# Adafruit_RGB_Matrix_FeatherWing_nRF52.net
KiCad netlist of a schematic drawn in EAGLE
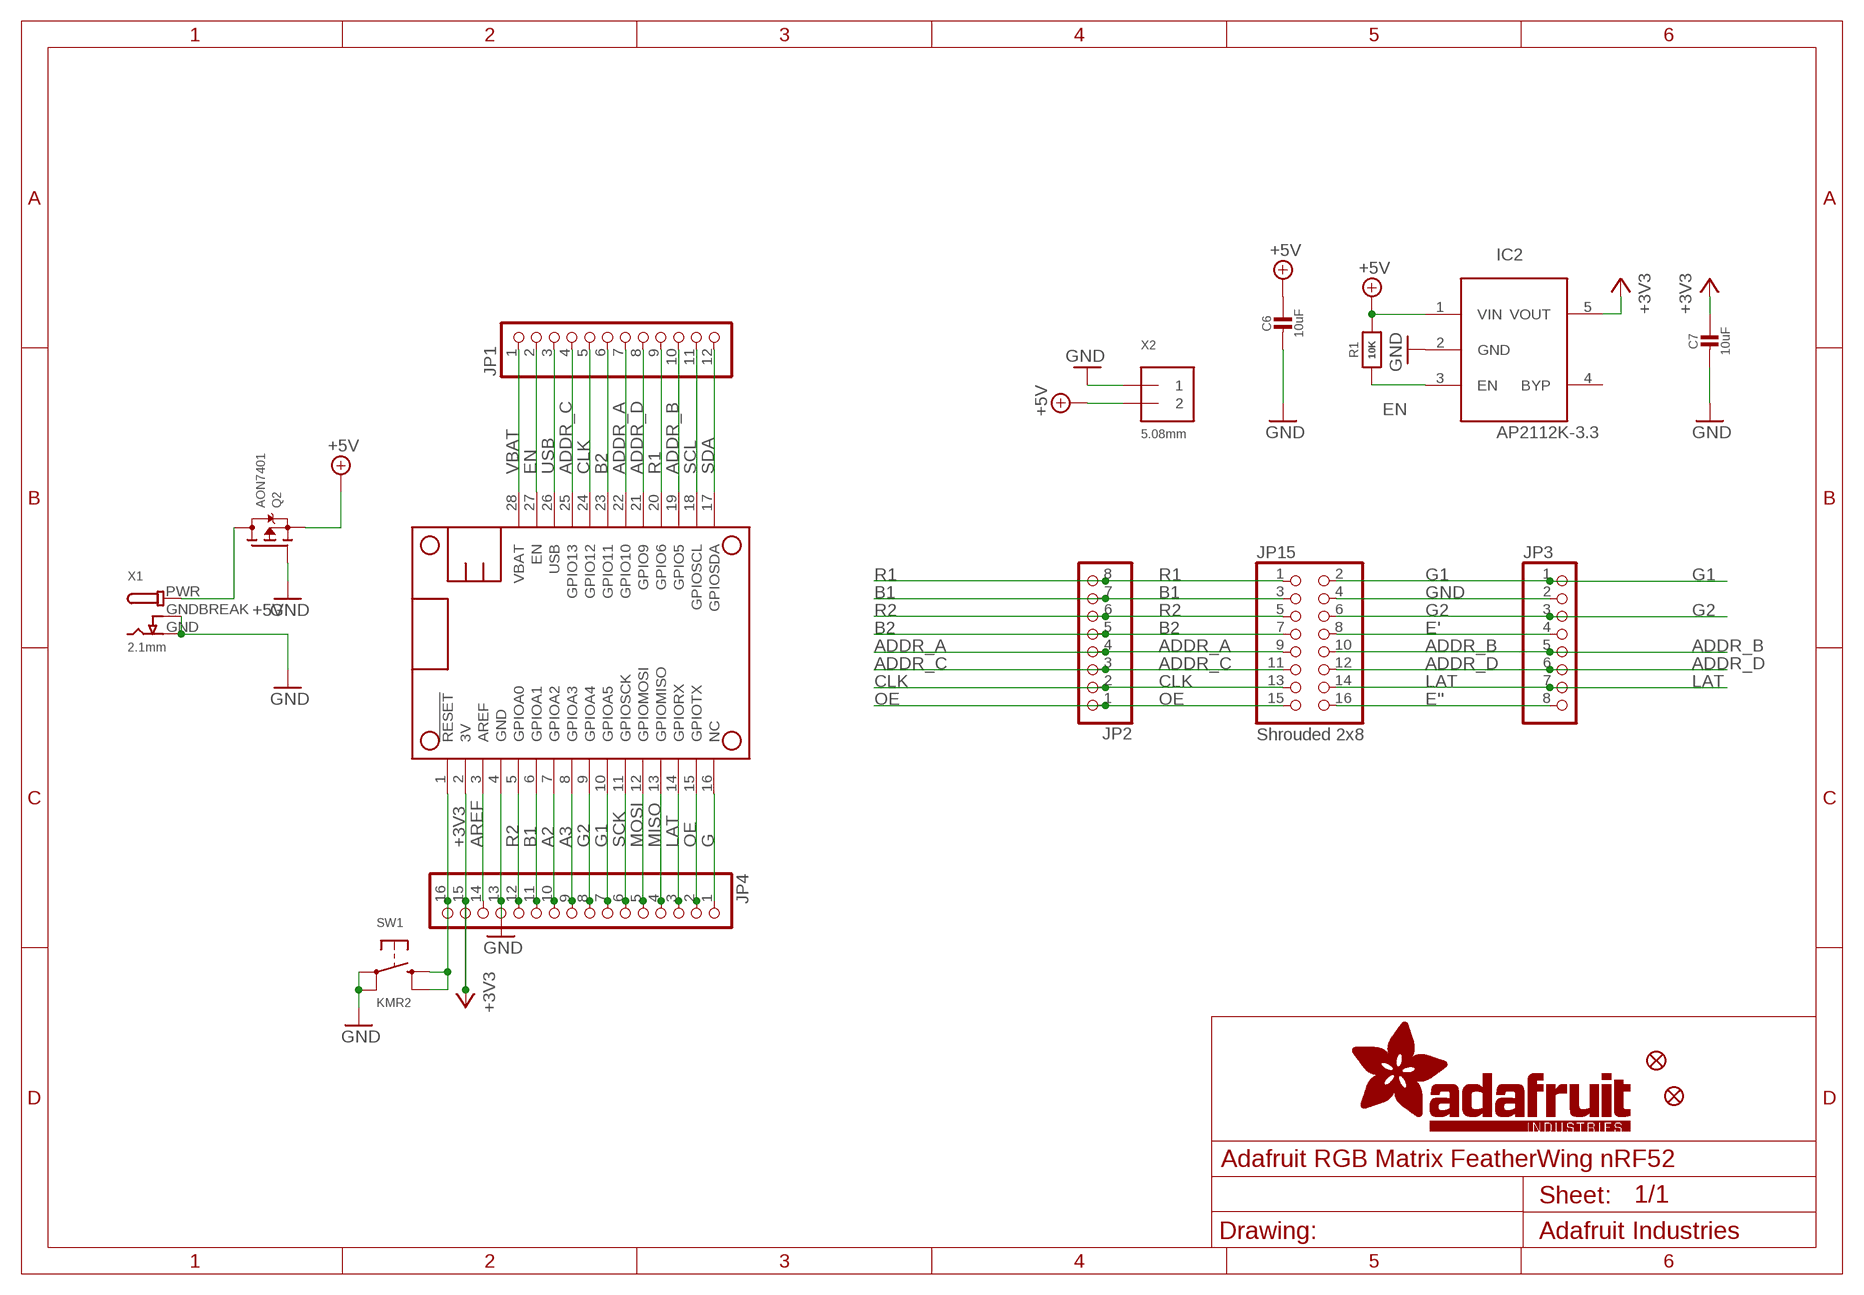
[diagram p0: schematic, sheet 1]

(export (version "E")
  (design (tool "Eeschema 10.0.6"))
  (components
    (comp (ref "C6")
      (value "10uF")
      (footprint "eagle-import:0805-NO")
      (libsource (lib "eagle-import") (part "CAP_CERAMIC0805-NOOUTLINE"))
    )
    (comp (ref "C7")
      (value "10uF")
      (footprint "eagle-import:0805-NO")
      (libsource (lib "eagle-import") (part "CAP_CERAMIC0805-NOOUTLINE"))
    )
    (comp (ref "FID1")
      (value "FIDUCIAL_1MM")
      (footprint "eagle-import:FIDUCIAL_1MM")
      (libsource (lib "eagle-import") (part "FIDUCIAL_1MM"))
    )
    (comp (ref "FID3")
      (value "FIDUCIAL_1MM")
      (footprint "eagle-import:FIDUCIAL_1MM")
      (libsource (lib "eagle-import") (part "FIDUCIAL_1MM"))
    )
    (comp (ref "IC2")
      (value "AP2112K-3.3")
      (footprint "eagle-import:SOT23-5L")
      (libsource (lib "eagle-import") (part "LP298XS"))
    )
    (comp (ref "JP1")
      (value "HEADER-1X12")
      (footprint "eagle-import:1X12_ROUND")
      (libsource (lib "eagle-import") (part "HEADER-1X12"))
    )
    (comp (ref "JP2")
      (value "HEADER-1X870MIL")
      (footprint "eagle-import:1X08_ROUND_70")
      (libsource (lib "eagle-import") (part "HEADER-1X870MIL"))
    )
    (comp (ref "JP3")
      (value "HEADER-1X870MIL")
      (footprint "eagle-import:1X08_ROUND_70")
      (libsource (lib "eagle-import") (part "HEADER-1X870MIL"))
    )
    (comp (ref "JP4")
      (value "HEADER-1X16ROUND")
      (footprint "eagle-import:1X16_ROUND")
      (libsource (lib "eagle-import") (part "HEADER-1X16ROUND"))
    )
    (comp (ref "JP15")
      (value "Shrouded 2x8")
      (footprint "eagle-import:2X08_SHROUDED")
      (libsource (lib "eagle-import") (part "HEADER-2X8_SHROUDED"))
    )
    (comp (ref "MS1")
      (value "FEATHERWING")
      (footprint "eagle-import:FEATHERWING")
      (libsource (lib "eagle-import") (part "FEATHERWING"))
    )
    (comp (ref "Q2")
      (value "AON7401")
      (footprint "eagle-import:POWERDI3333")
      (libsource (lib "eagle-import") (part "MOSFET-P-POWERDI3333"))
    )
    (comp (ref "R1")
      (value "10K")
      (footprint "eagle-import:0603-NO")
      (libsource (lib "eagle-import") (part "RESISTOR_0603_NOOUT"))
    )
    (comp (ref "SW1")
      (value "KMR2")
      (footprint "eagle-import:BTN_KMR2_4.6X2.8")
      (libsource (lib "eagle-import") (part "SWITCH_TACT_SMT4.6X2.8"))
    )
    (comp (ref "X1")
      (value "2.1mm")
      (footprint "eagle-import:DCJACK_2MM_PTH")
      (libsource (lib "eagle-import") (part "DCBARRELPTH"))
    )
    (comp (ref "X2")
      (value "5.08mm")
      (footprint "eagle-import:TERMBLOCK_508_1X2")
      (libsource (lib "eagle-import") (part "TERMBLOCK_1X2_5.08MM"))
    )
  )
  (nets
    (net (code "1") (name "+3V3") (class "Default")
      (node (ref "C7") (pin "1") (pinfunction "1_1") (pintype "passive"))
      (node (ref "IC2") (pin "5") (pinfunction "VOUT_5") (pintype "bidirectional"))
      (node (ref "JP4") (pin "15") (pinfunction "15_15") (pintype "passive"))
      (node (ref "MS1") (pin "2") (pinfunction "3V_2") (pintype "power_in"))
    )
    (net (code "2") (name "+5V") (class "Default")
      (node (ref "C6") (pin "1") (pinfunction "1_1") (pintype "passive"))
      (node (ref "IC2") (pin "1") (pinfunction "VIN_1") (pintype "bidirectional"))
      (node (ref "Q2") (pin "1") (pinfunction "S_1") (pintype "passive"))
      (node (ref "Q2") (pin "2") (pinfunction "S_2") (pintype "passive"))
      (node (ref "Q2") (pin "3") (pinfunction "S_3") (pintype "passive"))
      (node (ref "R1") (pin "2") (pinfunction "2_2") (pintype "passive"))
      (node (ref "X2") (pin "P$4") (pinfunction "2_P$4") (pintype "passive"))
    )
    (net (code "3") (name "/A2") (class "Default")
      (node (ref "JP4") (pin "10") (pinfunction "10_10") (pintype "passive"))
      (node (ref "MS1") (pin "7") (pinfunction "GPIOA2_7") (pintype "bidirectional"))
    )
    (net (code "4") (name "/A3") (class "Default")
      (node (ref "JP4") (pin "9") (pinfunction "9_9") (pintype "passive"))
      (node (ref "MS1") (pin "8") (pinfunction "GPIOA3_8") (pintype "bidirectional"))
    )
    (net (code "5") (name "/ADDR_A") (class "Default")
      (node (ref "JP1") (pin "7") (pinfunction "7_7") (pintype "passive"))
      (node (ref "JP15") (pin "9") (pinfunction "9_9") (pintype "passive"))
      (node (ref "JP2") (pin "4") (pinfunction "4_4") (pintype "passive"))
      (node (ref "MS1") (pin "22") (pinfunction "GPIO10_22") (pintype "bidirectional"))
    )
    (net (code "6") (name "/ADDR_B") (class "Default")
      (node (ref "JP1") (pin "10") (pinfunction "10_10") (pintype "passive"))
      (node (ref "JP15") (pin "10") (pinfunction "10_10") (pintype "passive"))
      (node (ref "JP3") (pin "5") (pinfunction "5_5") (pintype "passive"))
      (node (ref "MS1") (pin "19") (pinfunction "GPIO5_19") (pintype "bidirectional"))
    )
    (net (code "7") (name "/ADDR_C") (class "Default")
      (node (ref "JP1") (pin "4") (pinfunction "4_4") (pintype "passive"))
      (node (ref "JP15") (pin "11") (pinfunction "11_11") (pintype "passive"))
      (node (ref "JP2") (pin "3") (pinfunction "3_3") (pintype "passive"))
      (node (ref "MS1") (pin "25") (pinfunction "GPIO13_25") (pintype "bidirectional"))
    )
    (net (code "8") (name "/ADDR_D") (class "Default")
      (node (ref "JP1") (pin "8") (pinfunction "8_8") (pintype "passive"))
      (node (ref "JP15") (pin "12") (pinfunction "12_12") (pintype "passive"))
      (node (ref "JP3") (pin "6") (pinfunction "6_6") (pintype "passive"))
      (node (ref "MS1") (pin "21") (pinfunction "GPIO9_21") (pintype "bidirectional"))
    )
    (net (code "9") (name "/AREF") (class "Default")
      (node (ref "JP4") (pin "14") (pinfunction "14_14") (pintype "passive"))
      (node (ref "MS1") (pin "3") (pinfunction "AREF_3") (pintype "passive"))
    )
    (net (code "10") (name "/B1") (class "Default")
      (node (ref "JP15") (pin "3") (pinfunction "3_3") (pintype "passive"))
      (node (ref "JP2") (pin "7") (pinfunction "7_7") (pintype "passive"))
      (node (ref "JP4") (pin "11") (pinfunction "11_11") (pintype "passive"))
      (node (ref "MS1") (pin "6") (pinfunction "GPIOA1_6") (pintype "bidirectional"))
    )
    (net (code "11") (name "/B2") (class "Default")
      (node (ref "JP1") (pin "6") (pinfunction "6_6") (pintype "passive"))
      (node (ref "JP15") (pin "7") (pinfunction "7_7") (pintype "passive"))
      (node (ref "JP2") (pin "5") (pinfunction "5_5") (pintype "passive"))
      (node (ref "MS1") (pin "23") (pinfunction "GPIO11_23") (pintype "bidirectional"))
    )
    (net (code "12") (name "/CLK") (class "Default")
      (node (ref "JP1") (pin "5") (pinfunction "5_5") (pintype "passive"))
      (node (ref "JP15") (pin "13") (pinfunction "13_13") (pintype "passive"))
      (node (ref "JP2") (pin "2") (pinfunction "2_2") (pintype "passive"))
      (node (ref "MS1") (pin "24") (pinfunction "GPIO12_24") (pintype "bidirectional"))
    )
    (net (code "13") (name "/E'") (class "Default")
      (node (ref "JP15") (pin "8") (pinfunction "8_8") (pintype "passive"))
      (node (ref "JP3") (pin "4") (pinfunction "4_4") (pintype "passive"))
    )
    (net (code "14") (name "/E''") (class "Default")
      (node (ref "JP15") (pin "16") (pinfunction "16_16") (pintype "passive"))
      (node (ref "JP3") (pin "8") (pinfunction "8_8") (pintype "passive"))
    )
    (net (code "15") (name "/EN") (class "Default")
      (node (ref "IC2") (pin "3") (pinfunction "EN_3") (pintype "bidirectional"))
      (node (ref "JP1") (pin "2") (pinfunction "2_2") (pintype "passive"))
      (node (ref "MS1") (pin "27") (pinfunction "EN_27") (pintype "passive"))
      (node (ref "R1") (pin "1") (pinfunction "1_1") (pintype "passive"))
    )
    (net (code "16") (name "/G") (class "Default")
      (node (ref "JP4") (pin "1") (pinfunction "1_1") (pintype "passive"))
      (node (ref "MS1") (pin "16") (pinfunction "NC_16") (pintype "passive"))
    )
    (net (code "17") (name "/G1") (class "Default")
      (node (ref "JP15") (pin "2") (pinfunction "2_2") (pintype "passive"))
      (node (ref "JP3") (pin "1") (pinfunction "1_1") (pintype "passive"))
      (node (ref "JP4") (pin "7") (pinfunction "7_7") (pintype "passive"))
      (node (ref "MS1") (pin "10") (pinfunction "GPIOA5_10") (pintype "bidirectional"))
    )
    (net (code "18") (name "/G2") (class "Default")
      (node (ref "JP15") (pin "6") (pinfunction "6_6") (pintype "passive"))
      (node (ref "JP3") (pin "3") (pinfunction "3_3") (pintype "passive"))
      (node (ref "JP4") (pin "8") (pinfunction "8_8") (pintype "passive"))
      (node (ref "MS1") (pin "9") (pinfunction "GPIOA4_9") (pintype "bidirectional"))
    )
    (net (code "19") (name "/LAT") (class "Default")
      (node (ref "JP15") (pin "14") (pinfunction "14_14") (pintype "passive"))
      (node (ref "JP3") (pin "7") (pinfunction "7_7") (pintype "passive"))
      (node (ref "JP4") (pin "3") (pinfunction "3_3") (pintype "passive"))
      (node (ref "MS1") (pin "14") (pinfunction "GPIORX_14") (pintype "bidirectional"))
    )
    (net (code "20") (name "/MISO") (class "Default")
      (node (ref "JP4") (pin "4") (pinfunction "4_4") (pintype "passive"))
      (node (ref "MS1") (pin "13") (pinfunction "GPIOMISO_13") (pintype "bidirectional"))
    )
    (net (code "21") (name "/MOSI") (class "Default")
      (node (ref "JP4") (pin "5") (pinfunction "5_5") (pintype "passive"))
      (node (ref "MS1") (pin "12") (pinfunction "GPIOMOSI_12") (pintype "bidirectional"))
    )
    (net (code "22") (name "/OE") (class "Default")
      (node (ref "JP15") (pin "15") (pinfunction "15_15") (pintype "passive"))
      (node (ref "JP2") (pin "1") (pinfunction "1_1") (pintype "passive"))
      (node (ref "JP4") (pin "2") (pinfunction "2_2") (pintype "passive"))
      (node (ref "MS1") (pin "15") (pinfunction "GPIOTX_15") (pintype "bidirectional"))
    )
    (net (code "23") (name "/R1") (class "Default")
      (node (ref "JP1") (pin "9") (pinfunction "9_9") (pintype "passive"))
      (node (ref "JP15") (pin "1") (pinfunction "1_1") (pintype "passive"))
      (node (ref "JP2") (pin "8") (pinfunction "8_8") (pintype "passive"))
      (node (ref "MS1") (pin "20") (pinfunction "GPIO6_20") (pintype "bidirectional"))
    )
    (net (code "24") (name "/R2") (class "Default")
      (node (ref "JP15") (pin "5") (pinfunction "5_5") (pintype "passive"))
      (node (ref "JP2") (pin "6") (pinfunction "6_6") (pintype "passive"))
      (node (ref "JP4") (pin "12") (pinfunction "12_12") (pintype "passive"))
      (node (ref "MS1") (pin "5") (pinfunction "GPIOA0_5") (pintype "bidirectional"))
    )
    (net (code "25") (name "/SCK") (class "Default")
      (node (ref "JP4") (pin "6") (pinfunction "6_6") (pintype "passive"))
      (node (ref "MS1") (pin "11") (pinfunction "GPIOSCK_11") (pintype "bidirectional"))
    )
    (net (code "26") (name "/SCL") (class "Default")
      (node (ref "JP1") (pin "11") (pinfunction "11_11") (pintype "passive"))
      (node (ref "MS1") (pin "18") (pinfunction "GPIOSCL_18") (pintype "bidirectional"))
    )
    (net (code "27") (name "/SDA") (class "Default")
      (node (ref "JP1") (pin "12") (pinfunction "12_12") (pintype "passive"))
      (node (ref "MS1") (pin "17") (pinfunction "GPIOSDA_17") (pintype "bidirectional"))
    )
    (net (code "28") (name "/USB") (class "Default")
      (node (ref "JP1") (pin "3") (pinfunction "3_3") (pintype "passive"))
      (node (ref "MS1") (pin "26") (pinfunction "USB_26") (pintype "power_in"))
    )
    (net (code "29") (name "/VBAT") (class "Default")
      (node (ref "JP1") (pin "1") (pinfunction "1_1") (pintype "passive"))
      (node (ref "MS1") (pin "28") (pinfunction "VBAT_28") (pintype "power_in"))
    )
    (net (code "30") (name "GND") (class "Default")
      (node (ref "C6") (pin "2") (pinfunction "2_2") (pintype "passive"))
      (node (ref "C7") (pin "2") (pinfunction "2_2") (pintype "passive"))
      (node (ref "IC2") (pin "2") (pinfunction "GND_2") (pintype "bidirectional"))
      (node (ref "JP15") (pin "4") (pinfunction "4_4") (pintype "passive"))
      (node (ref "JP3") (pin "2") (pinfunction "2_2") (pintype "passive"))
      (node (ref "JP4") (pin "13") (pinfunction "13_13") (pintype "passive"))
      (node (ref "MS1") (pin "4") (pinfunction "GND_4") (pintype "power_in"))
      (node (ref "Q2") (pin "4") (pinfunction "G_4") (pintype "passive"))
      (node (ref "SW1") (pin "A") (pinfunction "P_A") (pintype "passive"))
      (node (ref "SW1") (pin "A'") (pinfunction "P1_A'") (pintype "passive"))
      (node (ref "X1") (pin "GND") (pinfunction "GND_GND") (pintype "power_in"))
      (node (ref "X1") (pin "GNDBREAK") (pinfunction "GNDBREAK_GNDBREAK") (pintype "power_in"))
      (node (ref "X2") (pin "P$3") (pinfunction "1_P$3") (pintype "passive"))
    )
    (net (code "31") (name "Net-(MS1-~{RESET})") (class "Default")
      (node (ref "JP4") (pin "16") (pinfunction "16_16") (pintype "passive"))
      (node (ref "MS1") (pin "1") (pinfunction "~{RESET}_1") (pintype "input"))
      (node (ref "SW1") (pin "B") (pinfunction "S_B") (pintype "passive"))
      (node (ref "SW1") (pin "B'") (pinfunction "S1_B'") (pintype "passive"))
    )
    (net (code "32") (name "Net-(Q2-D)") (class "Default")
      (node (ref "Q2") (pin "5678") (pinfunction "D_5678") (pintype "passive"))
      (node (ref "X1") (pin "PWR") (pinfunction "PWR_PWR") (pintype "power_in"))
    )
    (net (code "33") (name "unconnected-(IC2-BYP-Pad4)") (class "Default")
      (node (ref "IC2") (pin "4") (pinfunction "BYP_4") (pintype "bidirectional"))
    )
  )
)
